# PL2303_HX.net
KiCad netlist of a schematic drawn in Altium Designer
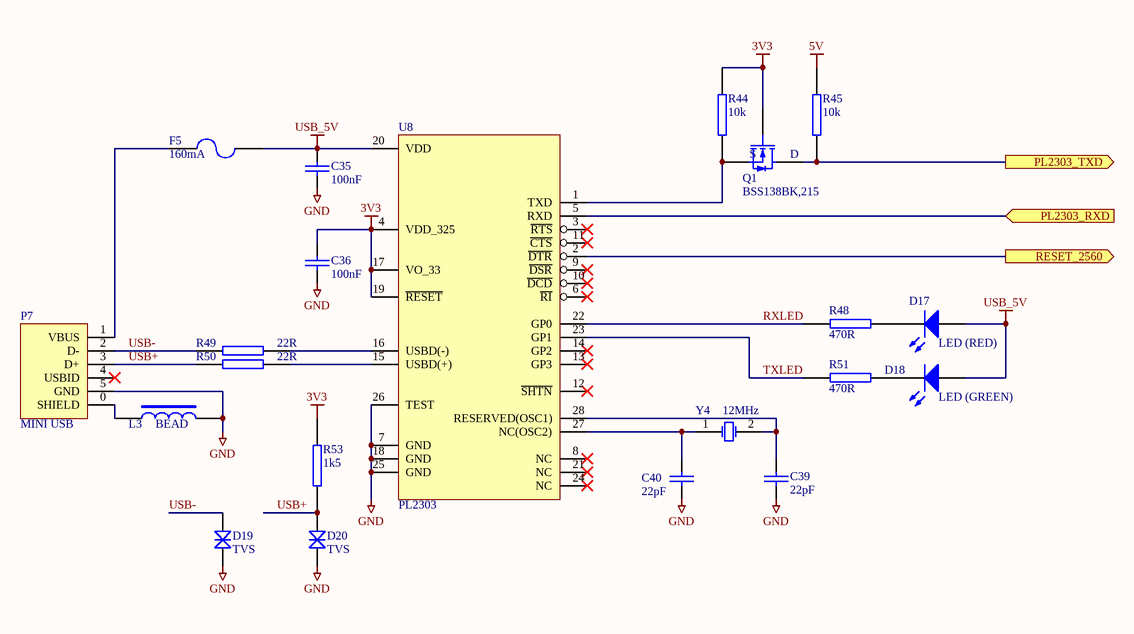
[diagram p0: PL2303(HX).SchDoc]

(export (version "E")
  (design (tool "Eeschema 10.0.6"))
  (components
    (comp (ref "C35")
      (value "100nF")
      (footprint "CAP (3D) - 0603")
      (description "CAPACITOR SMD 0603")
      (fields (field (name "MOUSER PART NO.") "81-GCM188R71C104KA7D") (field (name "MANUFACTURER") "Murata"))
      (libsource (lib "NASCO Capacitors") (part "CAP SMD 0603 100nF"))
    )
    (comp (ref "C36")
      (value "100nF")
      (footprint "CAP (3D) - 0603")
      (description "CAPACITOR SMD 0603")
      (fields (field (name "MOUSER PART NO.") "81-GCM188R71C104KA7D") (field (name "MANUFACTURER") "Murata"))
      (libsource (lib "NASCO Capacitors") (part "CAP SMD 0603 100nF"))
    )
    (comp (ref "C39")
      (value "22pF")
      (footprint "CAP (3D) - 0603")
      (description "CAPACITOR SMD 0603")
      (fields
        (field (name "MANUFACTURER") "Vishay")
        (field (name "MANUFACTURER PART NO.") "VJ0603A220JXACW1BC")
      )
      (libsource (lib "NASCO Capacitors") (part "CAP SMD 0603 1nF"))
    )
    (comp (ref "C40")
      (value "22pF")
      (footprint "CAP (3D) - 0603")
      (description "CAPACITOR SMD 0603")
      (fields
        (field (name "MANUFACTURER") "Vishay")
        (field (name "MANUFACTURER PART NO.") "VJ0603A220JXACW1BC")
      )
      (libsource (lib "NASCO Capacitors") (part "CAP SMD 0603 1nF"))
    )
    (comp (ref "D17")
      (value "LED (RED)")
      (footprint "LED(3D) 3MM VERTICAL (RED)")
      (description "3mm RED LED")
      (fields (field (name "MOUSER PART NO.") "859-LTL-4261NR") (field (name "MANUFACTURER") "Lite-On"))
      (libsource (lib "NASCO") (part "LED 3mm RED"))
    )
    (comp (ref "D18")
      (value "LED (GREEN)")
      (footprint "LED(3D) 3MM VERTICAL (GREEN)")
      (description "3mm GREEN LED")
      (fields (field (name "MOUSER PART NO.") "859-LTL-1CHG") (field (name "MANUFACTURER") "Lite-On"))
      (libsource (lib "NASCO") (part "LED 3mm GREEN"))
    )
    (comp (ref "D19")
      (value "TVS")
      (footprint "TVS (3D) - 0603")
      (description "Transient Voltage Suppression (TVS) Diode")
      (fields (field (name "MANUFACTURER PART NO.") "CG0603MLC-05E") (field (name "MANUFACTURER") "Bourns"))
      (libsource (lib "SIM900") (part "TVS DIODE"))
    )
    (comp (ref "D20")
      (value "TVS")
      (footprint "TVS (3D) - 0603")
      (description "Transient Voltage Suppression (TVS) Diode")
      (fields (field (name "MANUFACTURER PART NO.") "CG0603MLC-05E") (field (name "MANUFACTURER") "Bourns"))
      (libsource (lib "SIM900") (part "TVS DIODE"))
    )
    (comp (ref "F5")
      (value "160mA")
      (footprint "1206")
      (description "Fuse")
      (fields (field (name "MANUFACTURER") "Littlefuse") (field (name "MOUSER PART NO.") "576-1206L016WR"))
      (libsource (lib "Miscellaneous Devices") (part "Fuse 2"))
    )
    (comp (ref "L3")
      (value "BEAD")
      (footprint "RES (3D) - 1210")
      (description "INDUCTOR SMD 1210")
      (fields (field (name "MOUSER PART NO.") "636-2512063007Y3") (field (name "MANUFACTURER") "Fair-Rite"))
      (libsource (lib "NASCO") (part "INDUCTOR SMD 1210 100uH"))
    )
    (comp (ref "P7")
      (value "MINI USB")
      (footprint "MINI USB")
      (description "MICRO USB")
      (fields
        (field (name "MANUFACTURER") "Keystone Electronics")
        (field (name "MANUFACTURER PART NO.") "534-934")
      )
      (libsource (lib "SIM900") (part "MICRO USB"))
    )
    (comp (ref "Q1")
      (value "BSS138BK,215")
      (footprint "SOT23-3L")
      (description "N-Channel MOSFET")
      (fields
        (field (name "MANUFACTURER") "NXP Semiconductors")
        (field (name "MOUSER PART NO.") "771-BSS138BK215")
      )
      (libsource (lib "SIM900") (part "BSS138BK,215 SOT23"))
    )
    (comp (ref "R44")
      (value "10k")
      (footprint "RES (3D) - 0603")
      (description "RESISTOR SMD 0603 10k")
      (fields (field (name "MOUSER PART NO.") "652-CR0603FX-1002ELF") (field (name "MANUFACTURER") "Bourns"))
      (libsource (lib "NASCO Resistors") (part "RES SMD 0603 10k"))
    )
    (comp (ref "R45")
      (value "10k")
      (footprint "RES (3D) - 0603")
      (description "RESISTOR SMD 0603 10k")
      (fields (field (name "MOUSER PART NO.") "652-CR0603FX-1002ELF") (field (name "MANUFACTURER") "Bourns"))
      (libsource (lib "NASCO Resistors") (part "RES SMD 0603 10k"))
    )
    (comp (ref "R48")
      (value "470R")
      (footprint "RES (3D) - 0603")
      (description "RESISTOR SMD 0603 590R")
      (fields (field (name "MOUSER PART NO.") "71-CRCW0603J-470-E3") (field (name "MANUFACTURER") "Vishay"))
      (libsource (lib "NASCO Resistors") (part "RES SMD 0603 590R"))
    )
    (comp (ref "R49")
      (value "22R")
      (footprint "RES (3D) - 0603")
      (description "RESISTOR SMD 0603 0R")
      (fields (field (name "MANUFACTURER") "Xicon") (field (name "MANUFACTURER PART NO.") "301-22-RC"))
      (libsource (lib "NASCO Resistors") (part "RES SMD 0603 0R"))
    )
    (comp (ref "R50")
      (value "22R")
      (footprint "RES (3D) - 0603")
      (description "RESISTOR SMD 0603 0R")
      (fields (field (name "MANUFACTURER") "Xicon") (field (name "MANUFACTURER PART NO.") "301-22-RC"))
      (libsource (lib "NASCO Resistors") (part "RES SMD 0603 0R"))
    )
    (comp (ref "R51")
      (value "470R")
      (footprint "RES (3D) - 0603")
      (description "RESISTOR SMD 0603 590R")
      (fields (field (name "MOUSER PART NO.") "71-CRCW0603J-470-E3") (field (name "MANUFACTURER") "Vishay"))
      (libsource (lib "NASCO Resistors") (part "RES SMD 0603 590R"))
    )
    (comp (ref "R53")
      (value "1k5")
      (footprint "RES (3D) - 0603")
      (description "RESISTOR SMD 0603 0R")
      (libsource (lib "NASCO Resistors") (part "RES SMD 0603 0R"))
    )
    (comp (ref "U8")
      (value "PL2303")
      (footprint "SSOP28")
      (description "PL2303 USB to 232 Converter (FT232 Compatible)")
      (libsource (lib "NASCO") (part "PL2303"))
    )
    (comp (ref "Y4")
      (value "12MHz")
      (footprint "HC49/4H_SMX")
      (description "Crystal Oscillator")
      (fields (field (name "MANUFACTURER") "ECS"))
      (libsource (lib "Miscellaneous Devices") (part "XTAL"))
    )
  )
  (nets
    (net (code "1") (name "/PL2303_RXD") (class "Default")
      (node (ref "U8") (pin "5") (pinfunction "RXD_5") (pintype "passive"))
    )
    (net (code "2") (name "/PL2303_TXD") (class "Default")
      (node (ref "Q1") (pin "3") (pinfunction "D_3") (pintype "passive"))
      (node (ref "R45") (pin "1") (pinfunction "1_1") (pintype "passive"))
    )
    (net (code "3") (name "/RESET_2560") (class "Default")
      (node (ref "U8") (pin "2") (pinfunction "~{DTR}_2") (pintype "passive"))
    )
    (net (code "4") (name "/RXLED") (class "Default")
      (node (ref "R48") (pin "1") (pinfunction "1_1") (pintype "passive"))
      (node (ref "U8") (pin "22") (pinfunction "GP0_22") (pintype "passive"))
    )
    (net (code "5") (name "/TXLED") (class "Default")
      (node (ref "R51") (pin "1") (pinfunction "1_1") (pintype "passive"))
      (node (ref "U8") (pin "23") (pinfunction "GP1_23") (pintype "passive"))
    )
    (net (code "6") (name "/USB+") (class "Default")
      (node (ref "D20") (pin "2") (pinfunction "K_2") (pintype "passive"))
      (node (ref "P7") (pin "3") (pinfunction "D+_3") (pintype "passive"))
      (node (ref "R50") (pin "1") (pinfunction "1_1") (pintype "passive"))
      (node (ref "R53") (pin "2") (pinfunction "2_2") (pintype "passive"))
    )
    (net (code "7") (name "/USB-") (class "Default")
      (node (ref "D19") (pin "2") (pinfunction "K_2") (pintype "passive"))
      (node (ref "P7") (pin "2") (pinfunction "D-_2") (pintype "passive"))
      (node (ref "R49") (pin "1") (pinfunction "1_1") (pintype "passive"))
    )
    (net (code "8") (name "3V3") (class "Default")
      (node (ref "C36") (pin "1") (pinfunction "1_1") (pintype "passive"))
      (node (ref "Q1") (pin "1") (pinfunction "G_1") (pintype "passive"))
      (node (ref "R44") (pin "2") (pinfunction "2_2") (pintype "passive"))
      (node (ref "R53") (pin "1") (pinfunction "1_1") (pintype "passive"))
      (node (ref "U8") (pin "17") (pinfunction "VO_33_17") (pintype "passive"))
      (node (ref "U8") (pin "19") (pinfunction "~{RESET}_19") (pintype "passive"))
      (node (ref "U8") (pin "4") (pinfunction "VDD_325_4") (pintype "passive"))
    )
    (net (code "9") (name "5V") (class "Default")
      (node (ref "R45") (pin "2") (pinfunction "2_2") (pintype "passive"))
    )
    (net (code "10") (name "GND") (class "Default")
      (node (ref "C35") (pin "2") (pinfunction "2_2") (pintype "passive"))
      (node (ref "C36") (pin "2") (pinfunction "2_2") (pintype "passive"))
      (node (ref "C39") (pin "2") (pinfunction "2_2") (pintype "passive"))
      (node (ref "C40") (pin "2") (pinfunction "2_2") (pintype "passive"))
      (node (ref "D19") (pin "1") (pinfunction "A_1") (pintype "passive"))
      (node (ref "D20") (pin "1") (pinfunction "A_1") (pintype "passive"))
      (node (ref "L3") (pin "2") (pinfunction "2_2") (pintype "passive"))
      (node (ref "P7") (pin "5") (pinfunction "GND_5") (pintype "passive"))
      (node (ref "U8") (pin "18") (pinfunction "GND_18") (pintype "passive"))
      (node (ref "U8") (pin "25") (pinfunction "GND_25") (pintype "passive"))
      (node (ref "U8") (pin "26") (pinfunction "TEST_26") (pintype "passive"))
      (node (ref "U8") (pin "7") (pinfunction "GND_7") (pintype "passive"))
    )
    (net (code "11") (name "Net-(D17-K)") (class "Default")
      (node (ref "D17") (pin "2") (pinfunction "K_2") (pintype "passive"))
      (node (ref "R48") (pin "2") (pinfunction "2_2") (pintype "passive"))
    )
    (net (code "12") (name "Net-(D18-K)") (class "Default")
      (node (ref "D18") (pin "2") (pinfunction "K_2") (pintype "passive"))
      (node (ref "R51") (pin "2") (pinfunction "2_2") (pintype "passive"))
    )
    (net (code "13") (name "Net-(P7-SHIELD)") (class "Default")
      (node (ref "L3") (pin "1") (pinfunction "1_1") (pintype "passive"))
      (node (ref "P7") (pin "0") (pinfunction "SHIELD_0") (pintype "passive"))
    )
    (net (code "14") (name "Net-(P7-VBUS)") (class "Default")
      (node (ref "F5") (pin "1") (pinfunction "1_1") (pintype "passive"))
      (node (ref "P7") (pin "1") (pinfunction "VBUS_1") (pintype "passive"))
    )
    (net (code "15") (name "Net-(Q1-S)") (class "Default")
      (node (ref "Q1") (pin "2") (pinfunction "S_2") (pintype "passive"))
      (node (ref "R44") (pin "1") (pinfunction "1_1") (pintype "passive"))
      (node (ref "U8") (pin "1") (pinfunction "TXD_1") (pintype "passive"))
    )
    (net (code "16") (name "Net-(U8-NC(OSC2))") (class "Default")
      (node (ref "C40") (pin "1") (pinfunction "1_1") (pintype "passive"))
      (node (ref "U8") (pin "27") (pinfunction "NC(OSC2)_27") (pintype "passive"))
      (node (ref "Y4") (pin "1") (pinfunction "OSC1_1") (pintype "passive"))
    )
    (net (code "17") (name "Net-(U8-RESERVED(OSC1))") (class "Default")
      (node (ref "C39") (pin "1") (pinfunction "1_1") (pintype "passive"))
      (node (ref "U8") (pin "28") (pinfunction "RESERVED(OSC1)_28") (pintype "passive"))
      (node (ref "Y4") (pin "2") (pinfunction "OSC2_2") (pintype "passive"))
    )
    (net (code "18") (name "Net-(U8-USBD(+))") (class "Default")
      (node (ref "R50") (pin "2") (pinfunction "2_2") (pintype "passive"))
      (node (ref "U8") (pin "15") (pinfunction "USBD(+)_15") (pintype "passive"))
    )
    (net (code "19") (name "Net-(U8-USBD(-))") (class "Default")
      (node (ref "R49") (pin "2") (pinfunction "2_2") (pintype "passive"))
      (node (ref "U8") (pin "16") (pinfunction "USBD(-)_16") (pintype "passive"))
    )
    (net (code "20") (name "USB_5V") (class "Default")
      (node (ref "C35") (pin "1") (pinfunction "1_1") (pintype "passive"))
      (node (ref "D17") (pin "1") (pinfunction "A_1") (pintype "passive"))
      (node (ref "D18") (pin "1") (pinfunction "A_1") (pintype "passive"))
      (node (ref "F5") (pin "2") (pinfunction "2_2") (pintype "passive"))
      (node (ref "U8") (pin "20") (pinfunction "VDD_20") (pintype "passive"))
    )
    (net (code "21") (name "unconnected-(P7-USBID-Pad4)") (class "Default")
      (node (ref "P7") (pin "4") (pinfunction "USBID_4") (pintype "passive+no_connect"))
    )
    (net (code "22") (name "unconnected-(U8-GP2-Pad14)") (class "Default")
      (node (ref "U8") (pin "14") (pinfunction "GP2_14") (pintype "passive+no_connect"))
    )
    (net (code "23") (name "unconnected-(U8-GP3-Pad13)") (class "Default")
      (node (ref "U8") (pin "13") (pinfunction "GP3_13") (pintype "passive+no_connect"))
    )
    (net (code "24") (name "unconnected-(U8-NC-Pad8)") (class "Default")
      (node (ref "U8") (pin "8") (pinfunction "NC_8") (pintype "passive+no_connect"))
    )
    (net (code "25") (name "unconnected-(U8-NC-Pad21)") (class "Default")
      (node (ref "U8") (pin "21") (pinfunction "NC_21") (pintype "passive+no_connect"))
    )
    (net (code "26") (name "unconnected-(U8-NC-Pad24)") (class "Default")
      (node (ref "U8") (pin "24") (pinfunction "NC_24") (pintype "passive+no_connect"))
    )
    (net (code "27") (name "unconnected-(U8-~{CTS}-Pad11)") (class "Default")
      (node (ref "U8") (pin "11") (pinfunction "~{CTS}_11") (pintype "passive+no_connect"))
    )
    (net (code "28") (name "unconnected-(U8-~{DCD}-Pad10)") (class "Default")
      (node (ref "U8") (pin "10") (pinfunction "~{DCD}_10") (pintype "passive+no_connect"))
    )
    (net (code "29") (name "unconnected-(U8-~{DSR}-Pad9)") (class "Default")
      (node (ref "U8") (pin "9") (pinfunction "~{DSR}_9") (pintype "passive+no_connect"))
    )
    (net (code "30") (name "unconnected-(U8-~{RI}-Pad6)") (class "Default")
      (node (ref "U8") (pin "6") (pinfunction "~{RI}_6") (pintype "passive+no_connect"))
    )
    (net (code "31") (name "unconnected-(U8-~{RTS}-Pad3)") (class "Default")
      (node (ref "U8") (pin "3") (pinfunction "~{RTS}_3") (pintype "passive+no_connect"))
    )
    (net (code "32") (name "unconnected-(U8-~{SHTN}-Pad12)") (class "Default")
      (node (ref "U8") (pin "12") (pinfunction "~{SHTN}_12") (pintype "passive+no_connect"))
    )
  )
)
